# BSPDInputs.net
KiCad netlist of a schematic drawn in Altium Designer
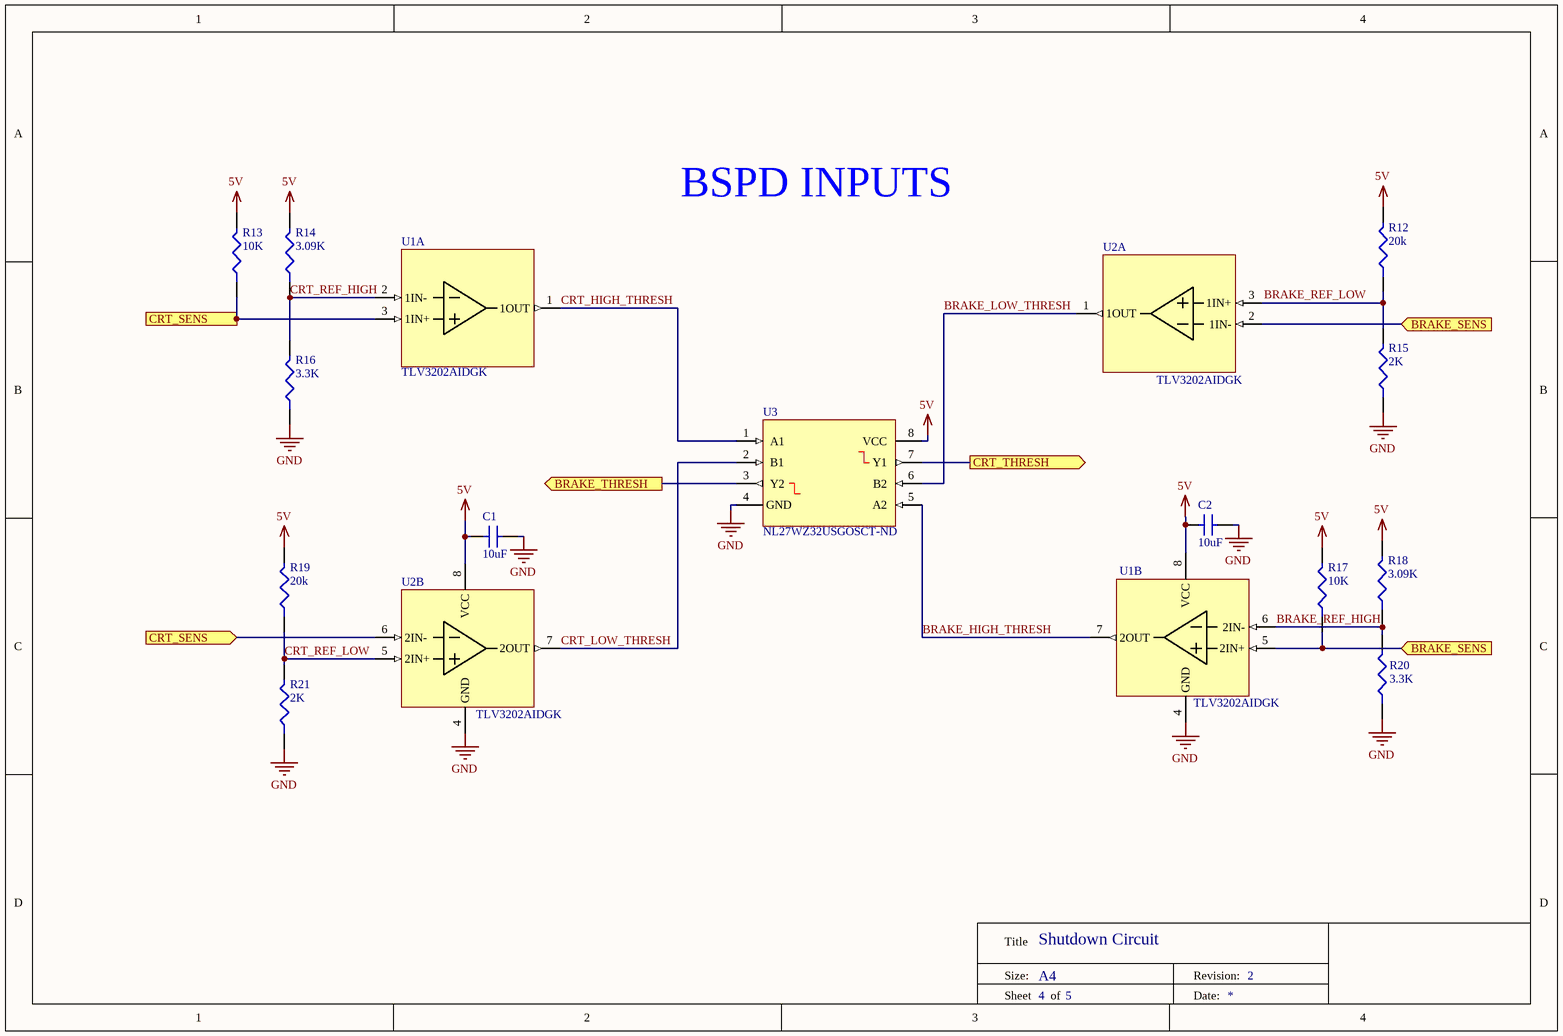
[diagram p0: BSPDInputs.SchDoc]

(export (version "E")
  (design (tool "Eeschema 10.0.6"))
  (components
    (comp (ref "C1")
      (value "10uF")
      (footprint "C0805")
      (description "Cap Ceramic 10uF 10V X5R 10% SMD 0805 85C Embossed T/R")
      (fields
        (field (name "MANUFACTURER") "Samsung")
        (field (name "MANUFACTURER PART NUMBER") "CL21A106KPFNNNG")
      )
      (libsource (lib "BSPD") (part "CL21A106KPFNNNG"))
    )
    (comp (ref "C2")
      (value "10uF")
      (footprint "C0805")
      (description "Cap Ceramic 10uF 10V X5R 10% SMD 0805 85C Embossed T/R")
      (fields
        (field (name "MANUFACTURER") "Samsung")
        (field (name "MANUFACTURER PART NUMBER") "CL21A106KPFNNNG")
      )
      (libsource (lib "BSPD") (part "CL21A106KPFNNNG"))
    )
    (comp (ref "R12")
      (value "20k")
      (footprint "RESC1608X06N")
      (fields
        (field (name "MANUFACTURER") "Yageo")
        (field (name "MANUFACTURER PART NUMBER") "RC0603FR-0722KL")
        (field (name "TOLERANCE") "1%")
      )
      (libsource (lib "BSPD") (part "RC0603FR-0722KL"))
    )
    (comp (ref "R13")
      (value "10K")
      (footprint "R0805")
      (description "RES SMD 10K OHM 0.1% 1/8W 0805")
      (fields
        (field (name "MANUFACTURER") "Panasonic")
        (field (name "MANUFACTURER PART NUMBER") "ERA6AEB103V")
      )
      (libsource (lib "BSPD") (part "ERA6AEB103V"))
    )
    (comp (ref "R14")
      (value "3.09K")
      (footprint "ERJPB3")
      (description "RES SMD 3.09K OHM 0.1% 1/5W 0603")
      (fields
        (field (name "MANUFACTURER") "Panasonic")
        (field (name "MANUFACTURER PART NUMBER") "ERJ-PB3B3091V")
      )
      (libsource (lib "BSPD") (part "ERJ-PB3B3091V"))
    )
    (comp (ref "R15")
      (value "2K")
      (footprint "R0805")
      (description "RES SMD 2K OHM 0.1% 1/8W 0805")
      (fields
        (field (name "MANUFACTURER") "Panasonic")
        (field (name "MANUFACTURER PART NUMBER") "ERA6AEB202V")
      )
      (libsource (lib "BSPD") (part "ERA6AEB202V"))
    )
    (comp (ref "R16")
      (value "3.3K")
      (footprint "ERJPB3")
      (description "RES SMD 3.3K OHM 0.1% 1/5W 0603")
      (fields
        (field (name "MANUFACTURER") "Panasonic")
        (field (name "MANUFACTURER PART NUMBER") "ERJ-PB3B3301V")
      )
      (libsource (lib "BSPD") (part "ERJ-PB3B3301V"))
    )
    (comp (ref "R17")
      (value "10K")
      (footprint "R0805")
      (description "RES SMD 10K OHM 0.1% 1/8W 0805")
      (fields
        (field (name "MANUFACTURER") "Panasonic")
        (field (name "MANUFACTURER PART NUMBER") "ERA6AEB103V")
      )
      (libsource (lib "BSPD") (part "ERA6AEB103V"))
    )
    (comp (ref "R18")
      (value "3.09K")
      (footprint "ERJPB3")
      (description "RES SMD 3.09K OHM 0.1% 1/5W 0603")
      (fields
        (field (name "MANUFACTURER") "Panasonic")
        (field (name "MANUFACTURER PART NUMBER") "ERJ-PB3B3091V")
      )
      (libsource (lib "BSPD") (part "ERJ-PB3B3091V"))
    )
    (comp (ref "R19")
      (value "20k")
      (footprint "RESC1608X06N")
      (fields
        (field (name "MANUFACTURER") "Yageo")
        (field (name "MANUFACTURER PART NUMBER") "RC0603FR-0722KL")
        (field (name "TOLERANCE") "1%")
      )
      (libsource (lib "BSPD") (part "RC0603FR-0722KL"))
    )
    (comp (ref "R20")
      (value "3.3K")
      (footprint "ERJPB3")
      (description "RES SMD 3.3K OHM 0.1% 1/5W 0603")
      (fields
        (field (name "MANUFACTURER") "Panasonic")
        (field (name "MANUFACTURER PART NUMBER") "ERJ-PB3B3301V")
      )
      (libsource (lib "BSPD") (part "ERJ-PB3B3301V"))
    )
    (comp (ref "R21")
      (value "2K")
      (footprint "R0805")
      (description "RES SMD 2K OHM 0.1% 1/8W 0805")
      (fields
        (field (name "MANUFACTURER") "Panasonic")
        (field (name "MANUFACTURER PART NUMBER") "ERA6AEB202V")
      )
      (libsource (lib "BSPD") (part "ERA6AEB202V"))
    )
    (comp (ref "U1")
      (value "TLV3202AIDGK")
      (footprint "TLV3202AIDGK")
      (description "IC COMPAR PWR RRI DL PP 8VSSOP")
      (fields (field (name "MANUFACTURER") "Texas Instruments"))
      (libsource (lib "") (part "TLV3202AIDGK_1"))
    )
    (comp (ref "U2")
      (value "TLV3202AIDGK")
      (footprint "TLV3202AIDGK")
      (description "IC COMPAR PWR RRI DL PP 8VSSOP")
      (fields (field (name "MANUFACTURER") "Texas Instruments"))
      (libsource (lib "") (part "TLV3202AIDGK_2"))
    )
    (comp (ref "U3")
      (value "NL27WZ32USGOSCT-ND")
      (footprint "TSSOP50P310X90-8N")
      (description "IC GATE OR 2CH 2-INP US8")
      (fields
        (field (name "MANUFACTURER") "ON Semiconductor")
        (field (name "MANUFACTURER PART NUMBER") "NL27WZ32USG")
      )
      (libsource (lib "BSPD") (part "OR GATE"))
    )
  )
  (nets
    (net (code "1") (name "/BRAKE_HIGH_THRESH") (class "Default")
      (node (ref "U1") (pin "7") (pinfunction "2OUT_7") (pintype "output"))
      (node (ref "U3") (pin "5") (pinfunction "A2_5") (pintype "input"))
    )
    (net (code "2") (name "/BRAKE_LOW_THRESH") (class "Default")
      (node (ref "U2") (pin "1") (pinfunction "1OUT_1") (pintype "output"))
      (node (ref "U3") (pin "6") (pinfunction "B2_6") (pintype "input"))
    )
    (net (code "3") (name "/BRAKE_REF_HIGH") (class "Default")
      (node (ref "R18") (pin "1") (pinfunction "1_1") (pintype "passive"))
      (node (ref "R20") (pin "2") (pinfunction "2_2") (pintype "passive"))
      (node (ref "U1") (pin "6") (pinfunction "2IN-_6") (pintype "input"))
    )
    (net (code "5") (name "/BRAKE_REF_LOW") (class "Default")
      (node (ref "R12") (pin "1") (pinfunction "1_1") (pintype "passive"))
      (node (ref "R15") (pin "2") (pinfunction "2_2") (pintype "passive"))
      (node (ref "U2") (pin "3") (pinfunction "1IN+_3") (pintype "input"))
    )
    (net (code "6") (name "/BRAKE_SENS") (class "Default")
      (node (ref "R17") (pin "1") (pinfunction "1_1") (pintype "passive"))
      (node (ref "U1") (pin "5") (pinfunction "2IN+_5") (pintype "input"))
      (node (ref "U2") (pin "2") (pinfunction "1IN-_2") (pintype "input"))
    )
    (net (code "7") (name "/BRAKE_THRESH") (class "Default")
      (node (ref "U3") (pin "3") (pinfunction "Y2_3") (pintype "output"))
    )
    (net (code "8") (name "/CRT_HIGH_THRESH") (class "Default")
      (node (ref "U1") (pin "1") (pinfunction "1OUT_1") (pintype "output"))
      (node (ref "U3") (pin "1") (pinfunction "A1_1") (pintype "input"))
    )
    (net (code "9") (name "/CRT_LOW_THRESH") (class "Default")
      (node (ref "U2") (pin "7") (pinfunction "2OUT_7") (pintype "output"))
      (node (ref "U3") (pin "2") (pinfunction "B1_2") (pintype "input"))
    )
    (net (code "10") (name "/CRT_REF_HIGH") (class "Default")
      (node (ref "R14") (pin "1") (pinfunction "1_1") (pintype "passive"))
      (node (ref "R16") (pin "2") (pinfunction "2_2") (pintype "passive"))
      (node (ref "U1") (pin "2") (pinfunction "1IN-_2") (pintype "input"))
    )
    (net (code "11") (name "/CRT_REF_LOW") (class "Default")
      (node (ref "R19") (pin "1") (pinfunction "1_1") (pintype "passive"))
      (node (ref "R21") (pin "2") (pinfunction "2_2") (pintype "passive"))
      (node (ref "U2") (pin "5") (pinfunction "2IN+_5") (pintype "input"))
    )
    (net (code "12") (name "/CRT_SENS") (class "Default")
      (node (ref "R13") (pin "1") (pinfunction "1_1") (pintype "passive"))
      (node (ref "U1") (pin "3") (pinfunction "1IN+_3") (pintype "input"))
      (node (ref "U2") (pin "6") (pinfunction "2IN-_6") (pintype "input"))
    )
    (net (code "13") (name "/CRT_THRESH") (class "Default")
      (node (ref "U3") (pin "7") (pinfunction "Y1_7") (pintype "output"))
    )
    (net (code "14") (name "5V") (class "Default")
      (node (ref "C1") (pin "2") (pinfunction "2_2") (pintype "passive"))
      (node (ref "C2") (pin "2") (pinfunction "2_2") (pintype "passive"))
      (node (ref "R12") (pin "2") (pinfunction "2_2") (pintype "passive"))
      (node (ref "R13") (pin "2") (pinfunction "2_2") (pintype "passive"))
      (node (ref "R14") (pin "2") (pinfunction "2_2") (pintype "passive"))
      (node (ref "R17") (pin "2") (pinfunction "2_2") (pintype "passive"))
      (node (ref "R18") (pin "2") (pinfunction "2_2") (pintype "passive"))
      (node (ref "R19") (pin "2") (pinfunction "2_2") (pintype "passive"))
      (node (ref "U1") (pin "8") (pinfunction "VCC_8") (pintype "power_in"))
      (node (ref "U2") (pin "8") (pinfunction "VCC_8") (pintype "power_in"))
      (node (ref "U3") (pin "8") (pinfunction "VCC_8") (pintype "power_in"))
    )
    (net (code "15") (name "GND") (class "Default")
      (node (ref "C1") (pin "1") (pinfunction "1_1") (pintype "passive"))
      (node (ref "C2") (pin "1") (pinfunction "1_1") (pintype "passive"))
      (node (ref "R15") (pin "1") (pinfunction "1_1") (pintype "passive"))
      (node (ref "R16") (pin "1") (pinfunction "1_1") (pintype "passive"))
      (node (ref "R20") (pin "1") (pinfunction "1_1") (pintype "passive"))
      (node (ref "R21") (pin "1") (pinfunction "1_1") (pintype "passive"))
      (node (ref "U1") (pin "4") (pinfunction "GND_4") (pintype "power_in"))
      (node (ref "U2") (pin "4") (pinfunction "GND_4") (pintype "power_in"))
      (node (ref "U3") (pin "4") (pinfunction "GND_4") (pintype "power_in"))
    )
  )
)
